# M8-1Wire.net
KiCad netlist of a schematic drawn in EAGLE
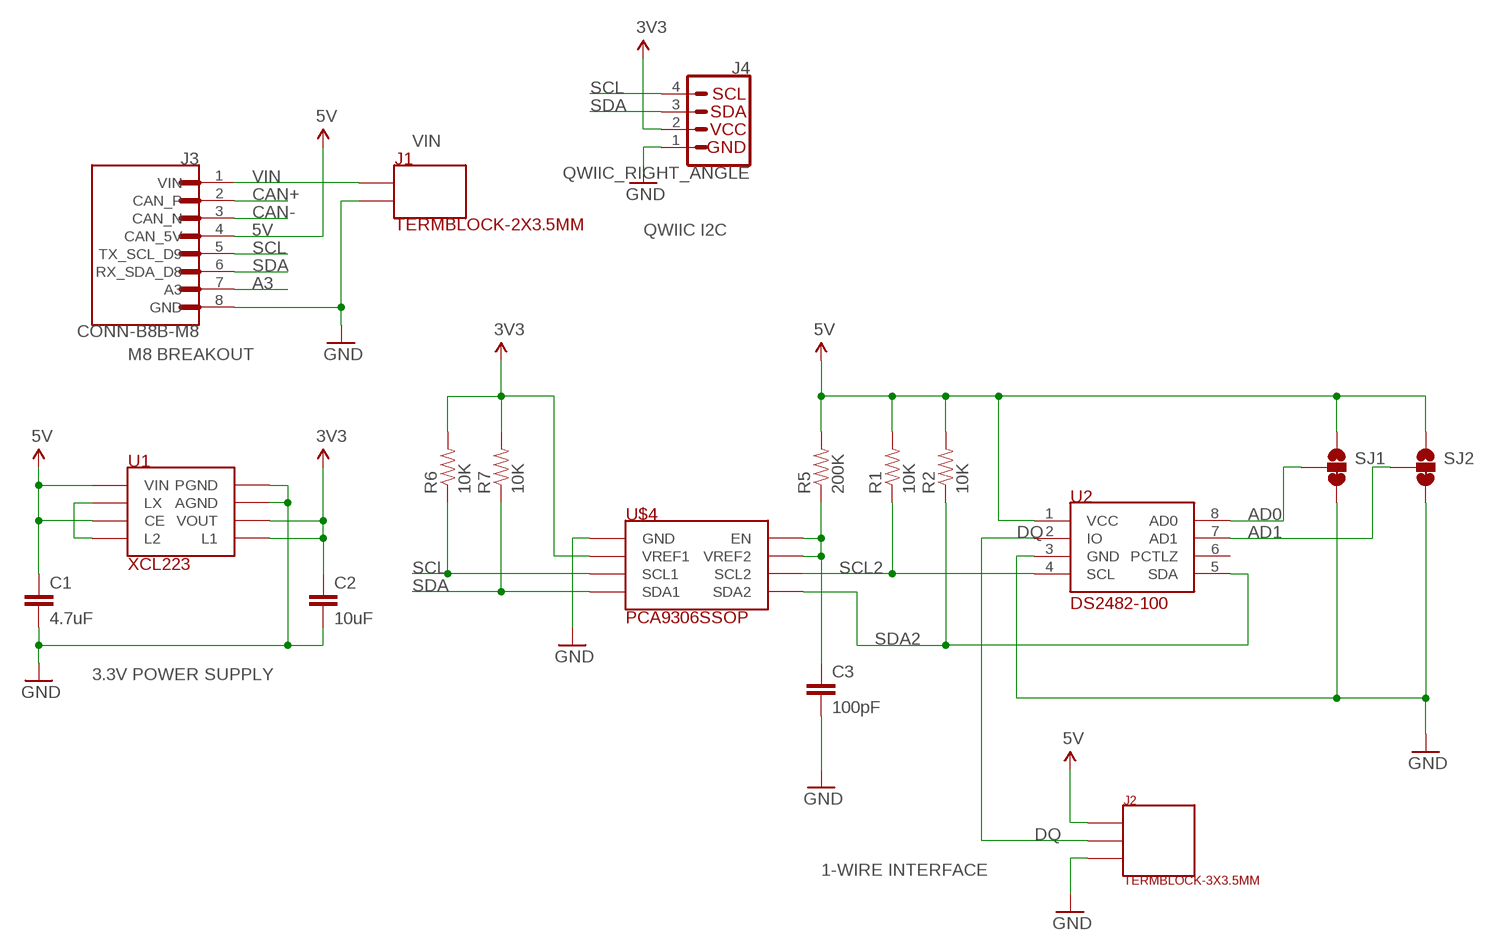
[diagram p0: schematic, sheet 1]

(export (version "E")
  (design (tool "Eeschema 10.0.6"))
  (components
    (comp (ref "C1")
      (value "4.7uF")
      (footprint "eagle-import:0603-CAP")
      (libsource (lib "eagle-import") (part "CAP-4.7UF-0603"))
    )
    (comp (ref "C2")
      (value "10uF")
      (footprint "eagle-import:0603-CAP")
      (libsource (lib "eagle-import") (part "CAP-10UF-0603"))
    )
    (comp (ref "C3")
      (value "100pF")
      (footprint "eagle-import:0603-CAP")
      (libsource (lib "eagle-import") (part "CAP-100PF-0603"))
    )
    (comp (ref "J1")
      (value "TERMBLOCK-2X3.5MM")
      (footprint "eagle-import:TERMBLOCK-2X3.5MM")
      (libsource (lib "eagle-import") (part "TERMBLOCK-2X3.5MM"))
    )
    (comp (ref "J2")
      (value "TERMBLOCK-3X3.5MM")
      (footprint "eagle-import:TERMBLOCK-3X3.5MM")
      (libsource (lib "eagle-import") (part "TERMBLOCK-3X3.5MM"))
    )
    (comp (ref "J3")
      (value "CONN-B8B-M8")
      (footprint "eagle-import:JST_B8B-PH-SM4-TB(LF)(SN)")
      (libsource (lib "eagle-import") (part "CONN-B8B-M8"))
    )
    (comp (ref "J4")
      (value "QWIIC_RIGHT_ANGLE")
      (footprint "eagle-import:JST04_1MM_RA")
      (libsource (lib "eagle-import") (part "QWIIC_CONNECTORJS-1MM"))
    )
    (comp (ref "R1")
      (value "10K")
      (footprint "eagle-import:0603-RES")
      (libsource (lib "eagle-import") (part "RES-10K-06030603"))
    )
    (comp (ref "R2")
      (value "10K")
      (footprint "eagle-import:0603-RES")
      (libsource (lib "eagle-import") (part "RES-10K-06030603"))
    )
    (comp (ref "R5")
      (value "200K")
      (footprint "eagle-import:0603-RES")
      (libsource (lib "eagle-import") (part "RES-200K-0603"))
    )
    (comp (ref "R6")
      (value "10K")
      (footprint "eagle-import:0603-RES")
      (libsource (lib "eagle-import") (part "RES-10K-06030603"))
    )
    (comp (ref "R7")
      (value "10K")
      (footprint "eagle-import:0603-RES")
      (libsource (lib "eagle-import") (part "RES-10K-06030603"))
    )
    (comp (ref "SJ1")
      (value "JUMPER-PAD-3-2OF3_NC_BY_TRACE_SMALL")
      (footprint "eagle-import:PAD-JUMPER-3-2OF3_NC_BY_TRACE_NO_SILK")
      (libsource (lib "eagle-import") (part "JUMPER-PAD-3-2OF3_NC_BY_TRACE_SMALL"))
    )
    (comp (ref "SJ2")
      (value "JUMPER-PAD-3-2OF3_NC_BY_TRACE_SMALL")
      (footprint "eagle-import:PAD-JUMPER-3-2OF3_NC_BY_TRACE_NO_SILK")
      (libsource (lib "eagle-import") (part "JUMPER-PAD-3-2OF3_NC_BY_TRACE_SMALL"))
    )
    (comp (ref "U$4")
      (value "PCA9306SSOP")
      (footprint "eagle-import:8-SSOP-TI")
      (libsource (lib "eagle-import") (part "PCA9306SSOP"))
    )
    (comp (ref "U1")
      (value "XCL223")
      (footprint "eagle-import:REG-XCL223-LESS-CREAM")
      (libsource (lib "eagle-import") (part "REG-XCL223"))
    )
    (comp (ref "U2")
      (value "DS2482-100")
      (footprint "eagle-import:8-SOIC-MAXIM")
      (libsource (lib "eagle-import") (part "DS2482-100"))
    )
  )
  (nets
    (net (code "1") (name "/A3") (class "Default")
      (node (ref "J3") (pin "7") (pinfunction "A3_7") (pintype "passive"))
    )
    (net (code "2") (name "/AD0") (class "Default")
      (node (ref "SJ1") (pin "2") (pinfunction "2_2") (pintype "passive"))
      (node (ref "U2") (pin "8") (pinfunction "AD0_8") (pintype "input"))
    )
    (net (code "3") (name "/AD1") (class "Default")
      (node (ref "SJ2") (pin "2") (pinfunction "2_2") (pintype "passive"))
      (node (ref "U2") (pin "7") (pinfunction "AD1_7") (pintype "input"))
    )
    (net (code "4") (name "/CAN+") (class "Default")
      (node (ref "J3") (pin "2") (pinfunction "CAN_P_2") (pintype "passive"))
    )
    (net (code "5") (name "/CAN-") (class "Default")
      (node (ref "J3") (pin "3") (pinfunction "CAN_N_3") (pintype "passive"))
    )
    (net (code "6") (name "/DQ") (class "Default")
      (node (ref "J2") (pin "2") (pinfunction "2_2") (pintype "passive"))
      (node (ref "U2") (pin "2") (pinfunction "IO_2") (pintype "bidirectional"))
    )
    (net (code "7") (name "/SCL") (class "Default")
      (node (ref "J3") (pin "5") (pinfunction "TX_SCL_D9_5") (pintype "passive"))
      (node (ref "J4") (pin "4") (pinfunction "4_4") (pintype "passive"))
      (node (ref "R6") (pin "1") (pinfunction "1_1") (pintype "passive"))
      (node (ref "U$4") (pin "3") (pinfunction "SCL1_3") (pintype "bidirectional"))
    )
    (net (code "8") (name "/SCL2") (class "Default")
      (node (ref "R1") (pin "1") (pinfunction "1_1") (pintype "passive"))
      (node (ref "U$4") (pin "6") (pinfunction "SCL2_6") (pintype "bidirectional"))
      (node (ref "U2") (pin "4") (pinfunction "SCL_4") (pintype "bidirectional"))
    )
    (net (code "9") (name "/SDA") (class "Default")
      (node (ref "J3") (pin "6") (pinfunction "RX_SDA_D8_6") (pintype "passive"))
      (node (ref "J4") (pin "3") (pinfunction "3_3") (pintype "passive"))
      (node (ref "R7") (pin "1") (pinfunction "1_1") (pintype "passive"))
      (node (ref "U$4") (pin "4") (pinfunction "SDA1_4") (pintype "bidirectional"))
    )
    (net (code "10") (name "/SDA2") (class "Default")
      (node (ref "R2") (pin "1") (pinfunction "1_1") (pintype "passive"))
      (node (ref "U$4") (pin "5") (pinfunction "SDA2_5") (pintype "bidirectional"))
      (node (ref "U2") (pin "5") (pinfunction "SDA_5") (pintype "bidirectional"))
    )
    (net (code "11") (name "/VIN") (class "Default")
      (node (ref "J1") (pin "1") (pinfunction "1_1") (pintype "passive"))
      (node (ref "J3") (pin "1") (pinfunction "VIN_1") (pintype "passive"))
    )
    (net (code "12") (name "3V3") (class "Default")
      (node (ref "C2") (pin "1") (pinfunction "1_1") (pintype "passive"))
      (node (ref "J4") (pin "2") (pinfunction "2_2") (pintype "power_in"))
      (node (ref "R6") (pin "2") (pinfunction "2_2") (pintype "passive"))
      (node (ref "R7") (pin "2") (pinfunction "2_2") (pintype "passive"))
      (node (ref "U$4") (pin "2") (pinfunction "VREF1_2") (pintype "power_in"))
      (node (ref "U1") (pin "3") (pinfunction "VOUT_3") (pintype "passive"))
      (node (ref "U1") (pin "7") (pinfunction "L1_7") (pintype "passive"))
    )
    (net (code "13") (name "5V") (class "Default")
      (node (ref "C1") (pin "1") (pinfunction "1_1") (pintype "passive"))
      (node (ref "J2") (pin "1") (pinfunction "1_1") (pintype "passive"))
      (node (ref "J3") (pin "4") (pinfunction "CAN_5V_4") (pintype "passive"))
      (node (ref "R1") (pin "2") (pinfunction "2_2") (pintype "passive"))
      (node (ref "R2") (pin "2") (pinfunction "2_2") (pintype "passive"))
      (node (ref "R5") (pin "2") (pinfunction "2_2") (pintype "passive"))
      (node (ref "SJ1") (pin "1") (pinfunction "1_1") (pintype "passive"))
      (node (ref "SJ2") (pin "1") (pinfunction "1_1") (pintype "passive"))
      (node (ref "U1") (pin "4") (pinfunction "CE_4") (pintype "input"))
      (node (ref "U1") (pin "6") (pinfunction "VIN_6") (pintype "power_in"))
      (node (ref "U2") (pin "1") (pinfunction "VCC_1") (pintype "power_in"))
    )
    (net (code "14") (name "GND") (class "Default")
      (node (ref "C1") (pin "2") (pinfunction "2_2") (pintype "passive"))
      (node (ref "C2") (pin "2") (pinfunction "2_2") (pintype "passive"))
      (node (ref "C3") (pin "2") (pinfunction "2_2") (pintype "passive"))
      (node (ref "J1") (pin "2") (pinfunction "2_2") (pintype "passive"))
      (node (ref "J2") (pin "3") (pinfunction "3_3") (pintype "passive"))
      (node (ref "J3") (pin "8") (pinfunction "GND_8") (pintype "passive"))
      (node (ref "J4") (pin "1") (pinfunction "1_1") (pintype "power_in"))
      (node (ref "SJ1") (pin "3") (pinfunction "3_3") (pintype "passive"))
      (node (ref "SJ2") (pin "3") (pinfunction "3_3") (pintype "passive"))
      (node (ref "U$4") (pin "1") (pinfunction "GND_1") (pintype "passive"))
      (node (ref "U1") (pin "1") (pinfunction "PGND_1") (pintype "passive"))
      (node (ref "U1") (pin "2") (pinfunction "AGND_2") (pintype "passive"))
      (node (ref "U2") (pin "3") (pinfunction "GND_3") (pintype "power_in"))
    )
    (net (code "15") (name "Net-(U$4-EN)") (class "Default")
      (node (ref "C3") (pin "1") (pinfunction "1_1") (pintype "passive"))
      (node (ref "R5") (pin "1") (pinfunction "1_1") (pintype "passive"))
      (node (ref "U$4") (pin "7") (pinfunction "VREF2_7") (pintype "input"))
      (node (ref "U$4") (pin "8") (pinfunction "EN_8") (pintype "input"))
    )
    (net (code "16") (name "Net-(U1-L2)") (class "Default")
      (node (ref "U1") (pin "5") (pinfunction "LX_5") (pintype "passive"))
      (node (ref "U1") (pin "8") (pinfunction "L2_8") (pintype "passive"))
    )
    (net (code "17") (name "unconnected-(U2-PCTLZ-Pad6)") (class "Default")
      (node (ref "U2") (pin "6") (pinfunction "PCTLZ_6") (pintype "output"))
    )
  )
)
